# sensor_sheild_mate.net
KiCad netlist of a schematic drawn in EAGLE
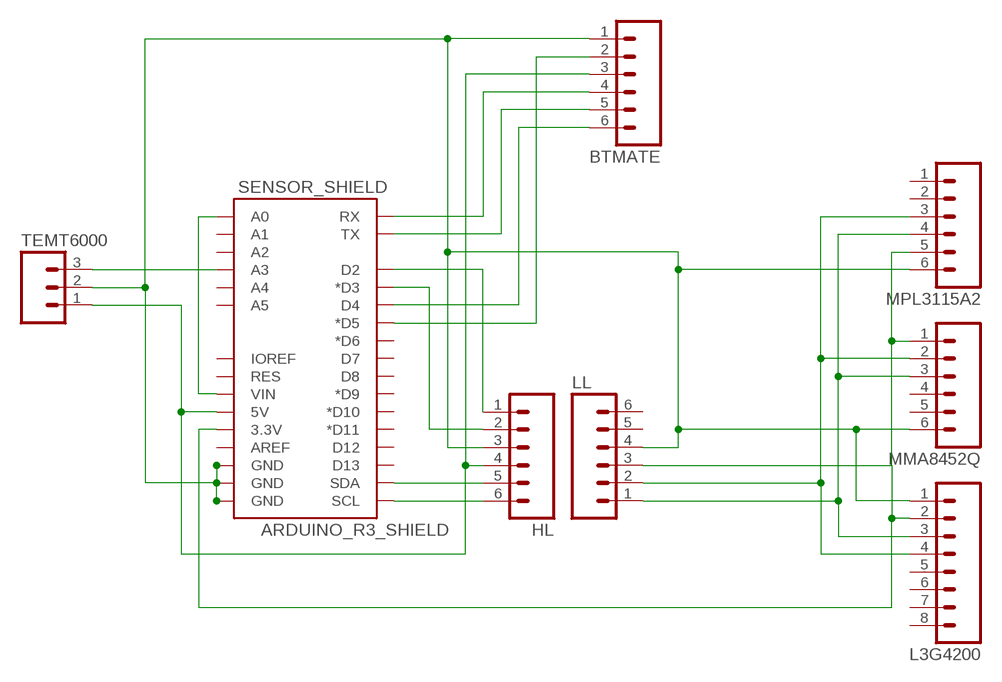
[diagram p0: schematic, sheet 1]

(export (version "E")
  (design (tool "Eeschema 10.0.6"))
  (components
    (comp (ref "BTMATE")
      (value "M06NO_SILK")
      (footprint "eagle-import:1X06_NO_SILK")
      (libsource (lib "eagle-import") (part "M06NO_SILK"))
    )
    (comp (ref "HL")
      (value "M06SIP")
      (footprint "eagle-import:1X06")
      (libsource (lib "eagle-import") (part "M06SIP"))
    )
    (comp (ref "L3G4200")
      (value "M08")
      (footprint "eagle-import:1X08_PIN1_NO_SILK")
      (libsource (lib "eagle-import") (part "M08"))
    )
    (comp (ref "LL")
      (value "M06SIP")
      (footprint "eagle-import:1X06")
      (libsource (lib "eagle-import") (part "M06SIP"))
    )
    (comp (ref "MMA8452Q")
      (value "M06SIP")
      (footprint "eagle-import:1X06")
      (libsource (lib "eagle-import") (part "M06SIP"))
    )
    (comp (ref "MPL3115A2")
      (value "M06SIP")
      (footprint "eagle-import:1X06")
      (libsource (lib "eagle-import") (part "M06SIP"))
    )
    (comp (ref "SENSOR_SHIELD")
      (value "ARDUINO_R3_SHIELD")
      (footprint "eagle-import:UNO_R3_SHIELD")
      (libsource (lib "eagle-import") (part "ARDUINO_R3_SHIELD"))
    )
    (comp (ref "TEMT6000")
      (value "M031X03_NO_SILK")
      (footprint "eagle-import:1X03_NO_SILK")
      (libsource (lib "eagle-import") (part "M031X03_NO_SILK"))
    )
  )
  (nets
    (net (code "1") (name "Net-(BTMATE-Pad1)") (class "Default")
      (node (ref "BTMATE") (pin "1") (pinfunction "1_1") (pintype "passive"))
      (node (ref "HL") (pin "3") (pinfunction "3_3") (pintype "passive"))
      (node (ref "L3G4200") (pin "1") (pinfunction "1_1") (pintype "passive"))
      (node (ref "LL") (pin "4") (pinfunction "4_4") (pintype "passive"))
      (node (ref "MMA8452Q") (pin "6") (pinfunction "6_6") (pintype "passive"))
      (node (ref "MPL3115A2") (pin "6") (pinfunction "6_6") (pintype "passive"))
      (node (ref "SENSOR_SHIELD") (pin "GND@0") (pinfunction "GND_GND@0") (pintype "bidirectional"))
      (node (ref "SENSOR_SHIELD") (pin "GND@1") (pinfunction "GND_GND@1") (pintype "bidirectional"))
      (node (ref "SENSOR_SHIELD") (pin "GND@2") (pinfunction "GND_GND@2") (pintype "bidirectional"))
      (node (ref "TEMT6000") (pin "2") (pinfunction "2_2") (pintype "passive"))
    )
    (net (code "2") (name "Net-(BTMATE-Pad3)") (class "Default")
      (node (ref "BTMATE") (pin "3") (pinfunction "3_3") (pintype "passive"))
      (node (ref "HL") (pin "4") (pinfunction "4_4") (pintype "passive"))
      (node (ref "SENSOR_SHIELD") (pin "5V") (pinfunction "5V_5V") (pintype "bidirectional"))
      (node (ref "TEMT6000") (pin "1") (pinfunction "1_1") (pintype "passive"))
    )
    (net (code "3") (name "Net-(BTMATE-Pad4)") (class "Default")
      (node (ref "BTMATE") (pin "4") (pinfunction "4_4") (pintype "passive"))
      (node (ref "SENSOR_SHIELD") (pin "RX") (pinfunction "RX_RX") (pintype "bidirectional"))
    )
    (net (code "4") (name "Net-(BTMATE-Pad5)") (class "Default")
      (node (ref "BTMATE") (pin "5") (pinfunction "5_5") (pintype "passive"))
      (node (ref "SENSOR_SHIELD") (pin "TX") (pinfunction "TX_TX") (pintype "bidirectional"))
    )
    (net (code "5") (name "Net-(BTMATE-Pad6)") (class "Default")
      (node (ref "BTMATE") (pin "6") (pinfunction "6_6") (pintype "passive"))
      (node (ref "SENSOR_SHIELD") (pin "D4") (pinfunction "D4_D4") (pintype "bidirectional"))
    )
    (net (code "6") (name "Net-(HL-Pad1)") (class "Default")
      (node (ref "HL") (pin "1") (pinfunction "1_1") (pintype "passive"))
      (node (ref "SENSOR_SHIELD") (pin "D2") (pinfunction "D2_D2") (pintype "bidirectional"))
    )
    (net (code "7") (name "Net-(HL-Pad5)") (class "Default")
      (node (ref "HL") (pin "5") (pinfunction "5_5") (pintype "passive"))
      (node (ref "SENSOR_SHIELD") (pin "SDA") (pinfunction "SDA_SDA") (pintype "bidirectional"))
    )
    (net (code "8") (name "Net-(HL-Pad6)") (class "Default")
      (node (ref "HL") (pin "6") (pinfunction "6_6") (pintype "passive"))
      (node (ref "SENSOR_SHIELD") (pin "SCL") (pinfunction "SCL_SCL") (pintype "bidirectional"))
    )
    (net (code "9") (name "Net-(L3G4200-Pad2)") (class "Default")
      (node (ref "L3G4200") (pin "2") (pinfunction "2_2") (pintype "passive"))
      (node (ref "LL") (pin "3") (pinfunction "3_3") (pintype "passive"))
      (node (ref "MMA8452Q") (pin "1") (pinfunction "1_1") (pintype "passive"))
      (node (ref "MPL3115A2") (pin "5") (pinfunction "5_5") (pintype "passive"))
      (node (ref "SENSOR_SHIELD") (pin "3.3V") (pinfunction "3.3V_3.3V") (pintype "bidirectional"))
    )
    (net (code "10") (name "Net-(L3G4200-Pad3)") (class "Default")
      (node (ref "L3G4200") (pin "3") (pinfunction "3_3") (pintype "passive"))
      (node (ref "LL") (pin "1") (pinfunction "1_1") (pintype "passive"))
      (node (ref "MMA8452Q") (pin "3") (pinfunction "3_3") (pintype "passive"))
      (node (ref "MPL3115A2") (pin "4") (pinfunction "4_4") (pintype "passive"))
    )
    (net (code "11") (name "Net-(L3G4200-Pad4)") (class "Default")
      (node (ref "L3G4200") (pin "4") (pinfunction "4_4") (pintype "passive"))
      (node (ref "LL") (pin "2") (pinfunction "2_2") (pintype "passive"))
      (node (ref "MMA8452Q") (pin "2") (pinfunction "2_2") (pintype "passive"))
      (node (ref "MPL3115A2") (pin "3") (pinfunction "3_3") (pintype "passive"))
    )
    (net (code "12") (name "Net-(SENSOR_SHIELD-*D3)") (class "Default")
      (node (ref "HL") (pin "2") (pinfunction "2_2") (pintype "passive"))
      (node (ref "SENSOR_SHIELD") (pin "D3") (pinfunction "*D3_D3") (pintype "bidirectional"))
    )
    (net (code "13") (name "Net-(SENSOR_SHIELD-*D5)") (class "Default")
      (node (ref "BTMATE") (pin "2") (pinfunction "2_2") (pintype "passive"))
      (node (ref "SENSOR_SHIELD") (pin "D5") (pinfunction "*D5_D5") (pintype "bidirectional"))
    )
    (net (code "14") (name "Net-(SENSOR_SHIELD-PadA0)") (class "Default")
      (node (ref "SENSOR_SHIELD") (pin "A0") (pinfunction "A0_A0") (pintype "bidirectional"))
      (node (ref "SENSOR_SHIELD") (pin "VIN") (pinfunction "VIN_VIN") (pintype "bidirectional"))
    )
    (net (code "15") (name "Net-(SENSOR_SHIELD-PadA3)") (class "Default")
      (node (ref "SENSOR_SHIELD") (pin "A3") (pinfunction "A3_A3") (pintype "bidirectional"))
      (node (ref "TEMT6000") (pin "3") (pinfunction "3_3") (pintype "passive"))
    )
    (net (code "16") (name "unconnected-(L3G4200-Pad5)") (class "Default")
      (node (ref "L3G4200") (pin "5") (pinfunction "5_5") (pintype "passive"))
    )
    (net (code "17") (name "unconnected-(L3G4200-Pad6)") (class "Default")
      (node (ref "L3G4200") (pin "6") (pinfunction "6_6") (pintype "passive"))
    )
    (net (code "18") (name "unconnected-(L3G4200-Pad7)") (class "Default")
      (node (ref "L3G4200") (pin "7") (pinfunction "7_7") (pintype "passive"))
    )
    (net (code "19") (name "unconnected-(L3G4200-Pad8)") (class "Default")
      (node (ref "L3G4200") (pin "8") (pinfunction "8_8") (pintype "passive"))
    )
    (net (code "20") (name "unconnected-(LL-Pad5)") (class "Default")
      (node (ref "LL") (pin "5") (pinfunction "5_5") (pintype "passive"))
    )
    (net (code "21") (name "unconnected-(LL-Pad6)") (class "Default")
      (node (ref "LL") (pin "6") (pinfunction "6_6") (pintype "passive"))
    )
    (net (code "22") (name "unconnected-(MMA8452Q-Pad4)") (class "Default")
      (node (ref "MMA8452Q") (pin "4") (pinfunction "4_4") (pintype "passive"))
    )
    (net (code "23") (name "unconnected-(MMA8452Q-Pad5)") (class "Default")
      (node (ref "MMA8452Q") (pin "5") (pinfunction "5_5") (pintype "passive"))
    )
    (net (code "24") (name "unconnected-(MPL3115A2-Pad1)") (class "Default")
      (node (ref "MPL3115A2") (pin "1") (pinfunction "1_1") (pintype "passive"))
    )
    (net (code "25") (name "unconnected-(MPL3115A2-Pad2)") (class "Default")
      (node (ref "MPL3115A2") (pin "2") (pinfunction "2_2") (pintype "passive"))
    )
    (net (code "26") (name "unconnected-(SENSOR_SHIELD-*D6-PadD6)") (class "Default")
      (node (ref "SENSOR_SHIELD") (pin "D6") (pinfunction "*D6_D6") (pintype "bidirectional"))
    )
    (net (code "27") (name "unconnected-(SENSOR_SHIELD-*D9-PadD9)") (class "Default")
      (node (ref "SENSOR_SHIELD") (pin "D9") (pinfunction "*D9_D9") (pintype "bidirectional"))
    )
    (net (code "28") (name "unconnected-(SENSOR_SHIELD-*D10-PadD10)") (class "Default")
      (node (ref "SENSOR_SHIELD") (pin "D10") (pinfunction "*D10_D10") (pintype "bidirectional"))
    )
    (net (code "29") (name "unconnected-(SENSOR_SHIELD-*D11-PadD11)") (class "Default")
      (node (ref "SENSOR_SHIELD") (pin "D11") (pinfunction "*D11_D11") (pintype "bidirectional"))
    )
    (net (code "30") (name "unconnected-(SENSOR_SHIELD-PadA1)") (class "Default")
      (node (ref "SENSOR_SHIELD") (pin "A1") (pinfunction "A1_A1") (pintype "bidirectional"))
    )
    (net (code "31") (name "unconnected-(SENSOR_SHIELD-PadA2)") (class "Default")
      (node (ref "SENSOR_SHIELD") (pin "A2") (pinfunction "A2_A2") (pintype "bidirectional"))
    )
    (net (code "32") (name "unconnected-(SENSOR_SHIELD-PadA4)") (class "Default")
      (node (ref "SENSOR_SHIELD") (pin "A4") (pinfunction "A4_A4") (pintype "bidirectional"))
    )
    (net (code "33") (name "unconnected-(SENSOR_SHIELD-PadA5)") (class "Default")
      (node (ref "SENSOR_SHIELD") (pin "A5") (pinfunction "A5_A5") (pintype "bidirectional"))
    )
    (net (code "34") (name "unconnected-(SENSOR_SHIELD-PadAREF)") (class "Default")
      (node (ref "SENSOR_SHIELD") (pin "AREF") (pinfunction "AREF_AREF") (pintype "bidirectional"))
    )
    (net (code "35") (name "unconnected-(SENSOR_SHIELD-PadD7)") (class "Default")
      (node (ref "SENSOR_SHIELD") (pin "D7") (pinfunction "D7_D7") (pintype "bidirectional"))
    )
    (net (code "36") (name "unconnected-(SENSOR_SHIELD-PadD8)") (class "Default")
      (node (ref "SENSOR_SHIELD") (pin "D8") (pinfunction "D8_D8") (pintype "bidirectional"))
    )
    (net (code "37") (name "unconnected-(SENSOR_SHIELD-PadD12)") (class "Default")
      (node (ref "SENSOR_SHIELD") (pin "D12") (pinfunction "D12_D12") (pintype "bidirectional"))
    )
    (net (code "38") (name "unconnected-(SENSOR_SHIELD-PadD13)") (class "Default")
      (node (ref "SENSOR_SHIELD") (pin "D13") (pinfunction "D13_D13") (pintype "bidirectional"))
    )
    (net (code "39") (name "unconnected-(SENSOR_SHIELD-PadIOREF)") (class "Default")
      (node (ref "SENSOR_SHIELD") (pin "IOREF") (pinfunction "IOREF_IOREF") (pintype "bidirectional"))
    )
    (net (code "40") (name "unconnected-(SENSOR_SHIELD-PadRES)") (class "Default")
      (node (ref "SENSOR_SHIELD") (pin "RES") (pinfunction "RES_RES") (pintype "bidirectional"))
    )
  )
)
